# amp_schematic2.net
KiCad netlist of a schematic drawn in EAGLE
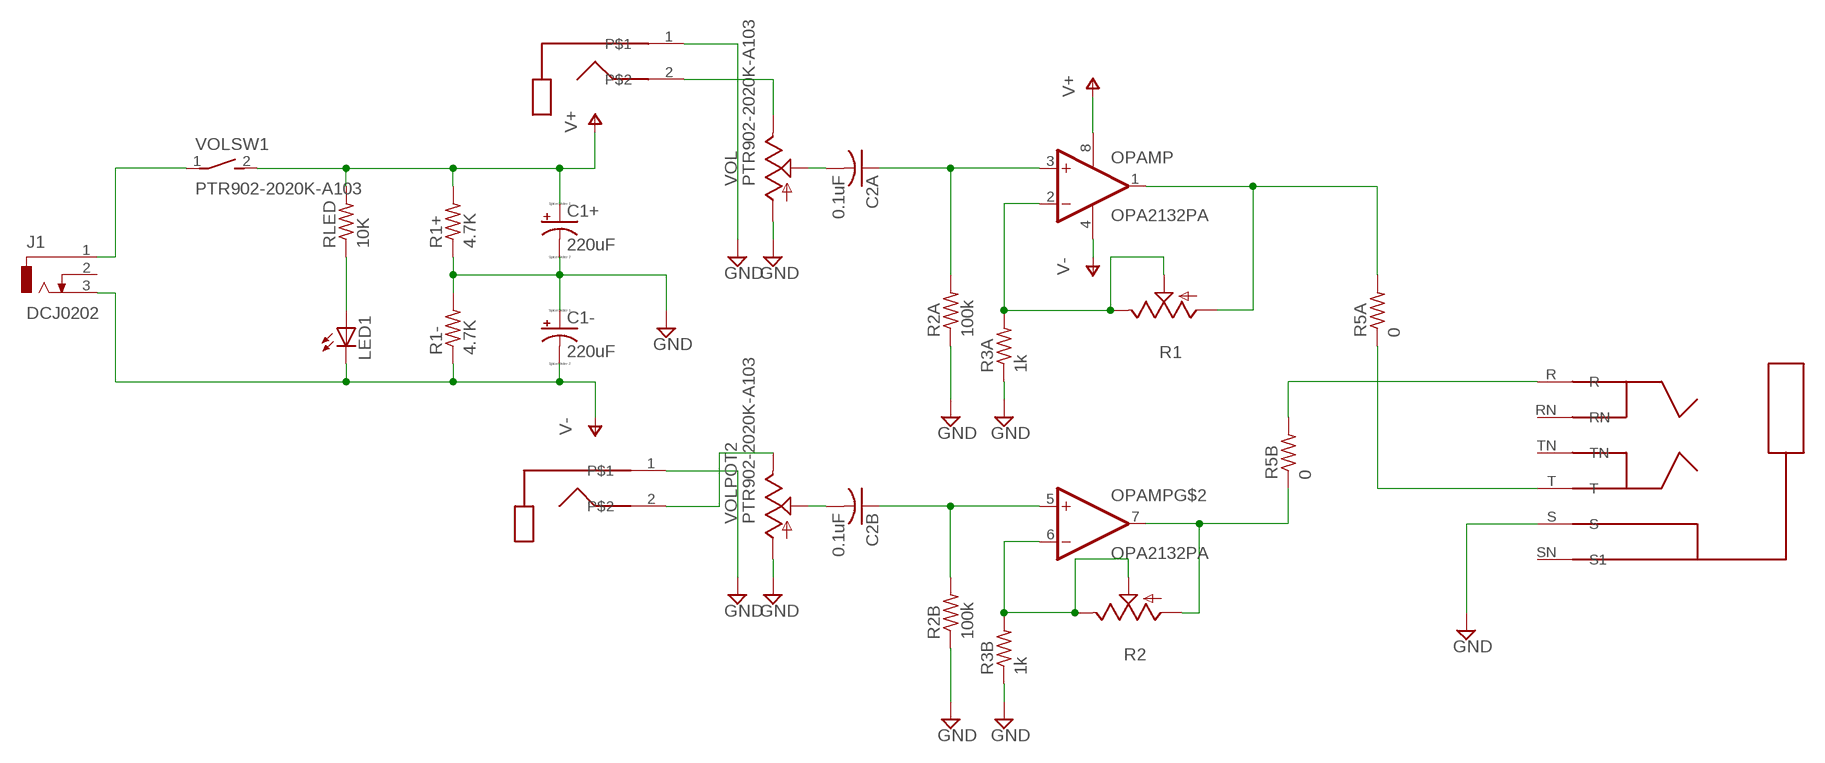
[diagram p0: schematic, sheet 1]

(export (version "E")
  (design (tool "Eeschema 10.0.6"))
  (components
    (comp (ref "C1+")
      (value "220uF")
      (footprint "eagle-import:E3,5-8")
      (libsource (lib "eagle-import") (part "CPOL-USE3.5-8"))
    )
    (comp (ref "C1-")
      (value "220uF")
      (footprint "eagle-import:E3,5-8")
      (libsource (lib "eagle-import") (part "CPOL-USE3.5-8"))
    )
    (comp (ref "C2A")
      (value "0.1uF")
      (footprint "eagle-import:C050-025X075")
      (libsource (lib "eagle-import") (part "C-US050-025X075"))
    )
    (comp (ref "C2B")
      (value "0.1uF")
      (footprint "eagle-import:C050-025X075")
      (libsource (lib "eagle-import") (part "C-US050-025X075"))
    )
    (comp (ref "J1")
      (value "DCJ0202")
      (footprint "eagle-import:DCJ0202")
      (libsource (lib "eagle-import") (part "DCJ0202"))
    )
    (comp (ref "LED1")
      (value "LED5MM")
      (footprint "eagle-import:LED5MM")
      (libsource (lib "eagle-import") (part "LED5MM"))
    )
    (comp (ref "LEFT")
      (value "RCAJACK")
      (footprint "eagle-import:RCAJACK")
      (libsource (lib "eagle-import") (part "RCAJACK"))
    )
    (comp (ref "OPAMP")
      (value "OPA2132PA")
      (footprint "eagle-import:DIP254P762X508-8")
      (fields (field (name "DIGI-KEY_PART_NUMBER") "OPA2132PA-ND") (field (name "MF") "Texas Instruments"))
      (libsource (lib "eagle-import") (part "OPA2132PA"))
    )
    (comp (ref "OUTPUT")
      (value "STEROJACK")
      (footprint "eagle-import:STEREOJACK")
      (libsource (lib "eagle-import") (part "STEROJACK"))
    )
    (comp (ref "R1")
      (value "TRIM_US-B25U")
      (footprint "eagle-import:B25U")
      (libsource (lib "eagle-import") (part "TRIM_US-B25U"))
    )
    (comp (ref "R1+")
      (value "4.7K")
      (footprint "eagle-import:0204V")
      (libsource (lib "eagle-import") (part "R-US_0204/2V"))
    )
    (comp (ref "R1-")
      (value "4.7K")
      (footprint "eagle-import:0204V")
      (libsource (lib "eagle-import") (part "R-US_0204/2V"))
    )
    (comp (ref "R2")
      (value "TRIM_US-B25U")
      (footprint "eagle-import:B25U")
      (libsource (lib "eagle-import") (part "TRIM_US-B25U"))
    )
    (comp (ref "R2A")
      (value "100k")
      (footprint "eagle-import:0204V")
      (libsource (lib "eagle-import") (part "R-US_0204/2V"))
    )
    (comp (ref "R2B")
      (value "100k")
      (footprint "eagle-import:0204V")
      (libsource (lib "eagle-import") (part "R-US_0204/2V"))
    )
    (comp (ref "R3A")
      (value "1k")
      (footprint "eagle-import:0204V")
      (libsource (lib "eagle-import") (part "R-US_0204/2V"))
    )
    (comp (ref "R3B")
      (value "1k")
      (footprint "eagle-import:0204V")
      (libsource (lib "eagle-import") (part "R-US_0204/2V"))
    )
    (comp (ref "R5A")
      (value "0")
      (footprint "eagle-import:0204V")
      (libsource (lib "eagle-import") (part "R-US_0204/2V"))
    )
    (comp (ref "R5B")
      (value "0")
      (footprint "eagle-import:0204V")
      (libsource (lib "eagle-import") (part "R-US_0204/2V"))
    )
    (comp (ref "RIGHT")
      (value "RCAJACK")
      (footprint "eagle-import:RCAJACK")
      (libsource (lib "eagle-import") (part "RCAJACK"))
    )
    (comp (ref "RLED")
      (value "10K")
      (footprint "eagle-import:0204V")
      (libsource (lib "eagle-import") (part "R-US_0204/2V"))
    )
    (comp (ref "VOL")
      (value "PTR902-2020K-A103")
      (footprint "eagle-import:PTR902")
      (libsource (lib "eagle-import") (part "PTR902-2020K-A103"))
    )
  )
  (nets
    (net (code "1") (name "GND") (class "Default")
      (node (ref "C1+") (pin "-") (pinfunction "-_-") (pintype "passive"))
      (node (ref "C1-") (pin "+") (pinfunction "+_+") (pintype "passive"))
      (node (ref "LEFT") (pin "1") (pinfunction "P$1_1") (pintype "bidirectional"))
      (node (ref "OUTPUT") (pin "S") (pinfunction "S_S") (pintype "bidirectional"))
      (node (ref "R1+") (pin "1") (pinfunction "1_1") (pintype "passive"))
      (node (ref "R1-") (pin "2") (pinfunction "2_2") (pintype "passive"))
      (node (ref "R2A") (pin "1") (pinfunction "1_1") (pintype "passive"))
      (node (ref "R2B") (pin "1") (pinfunction "1_1") (pintype "passive"))
      (node (ref "R3A") (pin "1") (pinfunction "1_1") (pintype "passive"))
      (node (ref "R3B") (pin "1") (pinfunction "1_1") (pintype "passive"))
      (node (ref "RIGHT") (pin "1") (pinfunction "P$1_1") (pintype "bidirectional"))
      (node (ref "VOL") (pin "1A") (pinfunction "A_1A") (pintype "passive"))
      (node (ref "VOL") (pin "1B") (pinfunction "A_1B") (pintype "passive"))
    )
    (net (code "2") (name "Net-(LED1-PadA)") (class "Default")
      (node (ref "LED1") (pin "A") (pinfunction "A_A") (pintype "passive"))
      (node (ref "RLED") (pin "1") (pinfunction "1_1") (pintype "passive"))
    )
    (net (code "3") (name "Net-(LEFT-P$2)") (class "Default")
      (node (ref "LEFT") (pin "2") (pinfunction "P$2_2") (pintype "bidirectional"))
      (node (ref "VOL") (pin "3A") (pinfunction "E_3A") (pintype "passive"))
    )
    (net (code "4") (name "Net-(OPAMPA-+INA)") (class "Default")
      (node (ref "C2A") (pin "1") (pinfunction "1_1") (pintype "passive"))
      (node (ref "OPAMP") (pin "3") (pinfunction "+INA_3") (pintype "input"))
      (node (ref "R2A") (pin "2") (pinfunction "2_2") (pintype "passive"))
    )
    (net (code "5") (name "Net-(OPAMPA--INA)") (class "Default")
      (node (ref "OPAMP") (pin "2") (pinfunction "-INA_2") (pintype "input"))
      (node (ref "R1") (pin "E") (pinfunction "E_E") (pintype "passive"))
      (node (ref "R1") (pin "S") (pinfunction "S_S") (pintype "passive"))
      (node (ref "R3A") (pin "2") (pinfunction "2_2") (pintype "passive"))
    )
    (net (code "6") (name "Net-(OPAMPA-OUTA)") (class "Default")
      (node (ref "OPAMP") (pin "1") (pinfunction "OUTA_1") (pintype "output"))
      (node (ref "R1") (pin "A") (pinfunction "A_A") (pintype "passive"))
      (node (ref "R5A") (pin "2") (pinfunction "2_2") (pintype "passive"))
    )
    (net (code "7") (name "Net-(OPAMPB-+INB)") (class "Default")
      (node (ref "C2B") (pin "1") (pinfunction "1_1") (pintype "passive"))
      (node (ref "OPAMP") (pin "5") (pinfunction "+INB_5") (pintype "input"))
      (node (ref "R2B") (pin "2") (pinfunction "2_2") (pintype "passive"))
    )
    (net (code "8") (name "Net-(OPAMPB--INB)") (class "Default")
      (node (ref "OPAMP") (pin "6") (pinfunction "-INB_6") (pintype "input"))
      (node (ref "R2") (pin "E") (pinfunction "E_E") (pintype "passive"))
      (node (ref "R2") (pin "S") (pinfunction "S_S") (pintype "passive"))
      (node (ref "R3B") (pin "2") (pinfunction "2_2") (pintype "passive"))
    )
    (net (code "9") (name "Net-(OPAMPB-OUTB)") (class "Default")
      (node (ref "OPAMP") (pin "7") (pinfunction "OUTB_7") (pintype "output"))
      (node (ref "R2") (pin "A") (pinfunction "A_A") (pintype "passive"))
      (node (ref "R5B") (pin "1") (pinfunction "1_1") (pintype "passive"))
    )
    (net (code "10") (name "Net-(OUTPUT-PadR)") (class "Default")
      (node (ref "OUTPUT") (pin "R") (pinfunction "R_R") (pintype "bidirectional"))
      (node (ref "R5B") (pin "2") (pinfunction "2_2") (pintype "passive"))
    )
    (net (code "11") (name "Net-(OUTPUT-PadT)") (class "Default")
      (node (ref "OUTPUT") (pin "T") (pinfunction "T_T") (pintype "bidirectional"))
      (node (ref "R5A") (pin "1") (pinfunction "1_1") (pintype "passive"))
    )
    (net (code "12") (name "Net-(RIGHT-P$2)") (class "Default")
      (node (ref "RIGHT") (pin "2") (pinfunction "P$2_2") (pintype "bidirectional"))
      (node (ref "VOL") (pin "3B") (pinfunction "E_3B") (pintype "passive"))
    )
    (net (code "13") (name "Net-(VOLA-S)") (class "Default")
      (node (ref "C2A") (pin "2") (pinfunction "2_2") (pintype "passive"))
      (node (ref "VOL") (pin "2A") (pinfunction "S_2A") (pintype "passive"))
    )
    (net (code "14") (name "Net-(VOLB-S)") (class "Default")
      (node (ref "C2B") (pin "2") (pinfunction "2_2") (pintype "passive"))
      (node (ref "VOL") (pin "2B") (pinfunction "S_2B") (pintype "passive"))
    )
    (net (code "15") (name "Net-(VOLC-P)") (class "Default")
      (node (ref "J1") (pin "1") (pinfunction "1_1") (pintype "passive"))
      (node (ref "VOL") (pin "1") (pinfunction "P_1") (pintype "passive"))
    )
    (net (code "16") (name "V+") (class "Default")
      (node (ref "C1+") (pin "+") (pinfunction "+_+") (pintype "passive"))
      (node (ref "OPAMP") (pin "8") (pinfunction "V+_8") (pintype "power_in"))
      (node (ref "R1+") (pin "2") (pinfunction "2_2") (pintype "passive"))
      (node (ref "RLED") (pin "2") (pinfunction "2_2") (pintype "passive"))
      (node (ref "VOL") (pin "2") (pinfunction "S_2") (pintype "passive"))
    )
    (net (code "17") (name "V-") (class "Default")
      (node (ref "C1-") (pin "-") (pinfunction "-_-") (pintype "passive"))
      (node (ref "J1") (pin "3") (pinfunction "3_3") (pintype "passive"))
      (node (ref "LED1") (pin "K") (pinfunction "C_K") (pintype "passive"))
      (node (ref "OPAMP") (pin "4") (pinfunction "V-_4") (pintype "power_in"))
      (node (ref "R1-") (pin "1") (pinfunction "1_1") (pintype "passive"))
    )
    (net (code "18") (name "unconnected-(J1-Pad2)") (class "Default")
      (node (ref "J1") (pin "2") (pinfunction "2_2") (pintype "passive"))
    )
    (net (code "19") (name "unconnected-(OUTPUT-PadRN)") (class "Default")
      (node (ref "OUTPUT") (pin "RN") (pinfunction "RN_RN") (pintype "bidirectional"))
    )
    (net (code "20") (name "unconnected-(OUTPUT-PadTN)") (class "Default")
      (node (ref "OUTPUT") (pin "TN") (pinfunction "TN_TN") (pintype "bidirectional"))
    )
    (net (code "21") (name "unconnected-(OUTPUT-S1-PadSN)") (class "Default")
      (node (ref "OUTPUT") (pin "SN") (pinfunction "S1_SN") (pintype "bidirectional"))
    )
  )
)
